# BRD171031.net
KiCad netlist of a schematic drawn in EAGLE
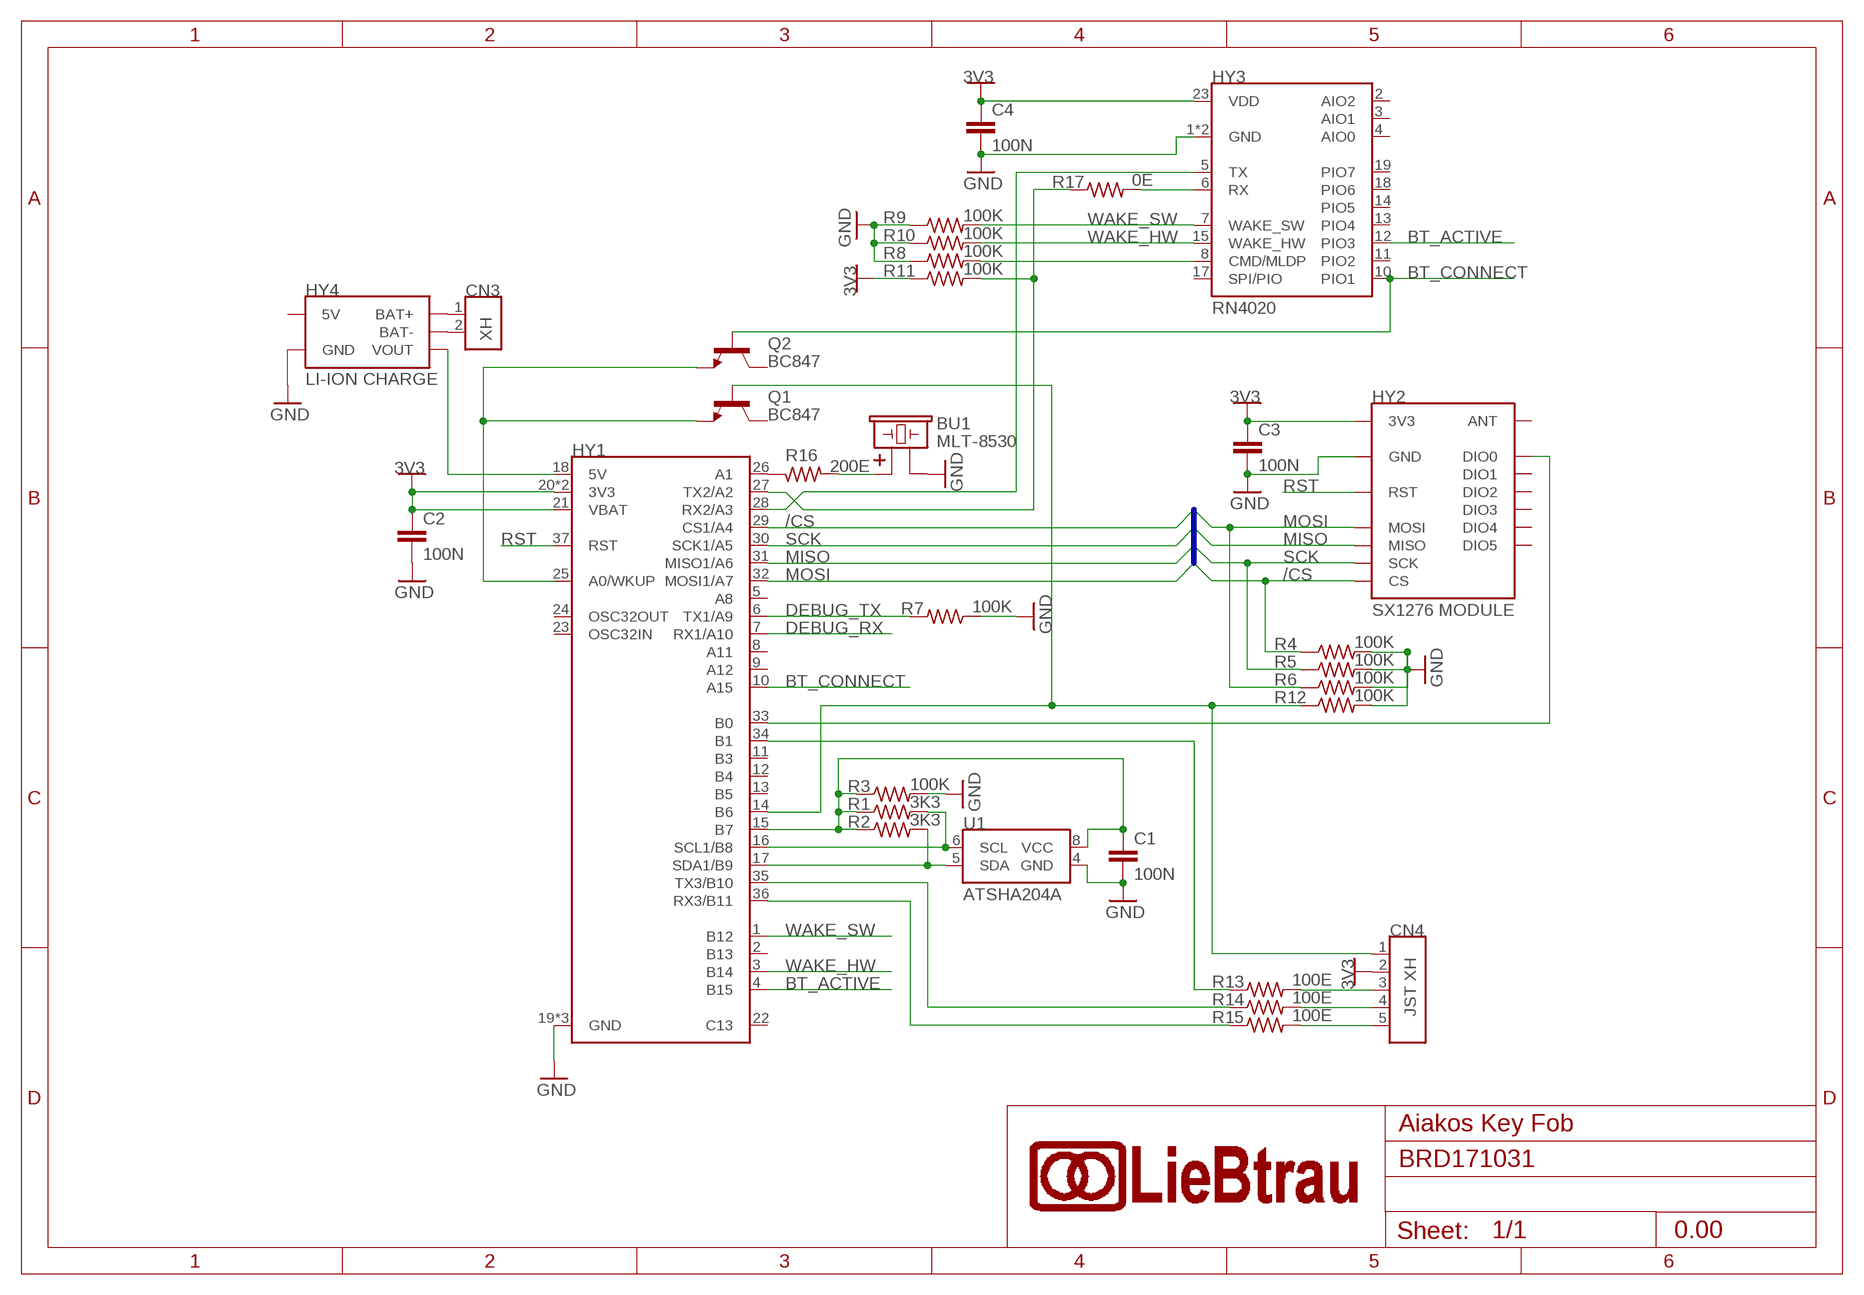
[diagram p0: schematic, sheet 1]

(export (version "E")
  (design (tool "Eeschema 10.0.6"))
  (components
    (comp (ref "BU1")
      (value "MLT-8530")
      (footprint "eagle-import:BU_8530")
      (libsource (lib "eagle-import") (part "BU_B2P8530_8530_"))
    )
    (comp (ref "C1")
      (value "100N")
      (footprint "eagle-import:CA_1206")
      (libsource (lib "eagle-import") (part "CA1206_100N_"))
    )
    (comp (ref "C2")
      (value "100N")
      (footprint "eagle-import:CA_1206")
      (libsource (lib "eagle-import") (part "CA1206_100N_"))
    )
    (comp (ref "C3")
      (value "100N")
      (footprint "eagle-import:CA_1206")
      (libsource (lib "eagle-import") (part "CA1206_100N_"))
    )
    (comp (ref "C4")
      (value "100N")
      (footprint "eagle-import:CA_1206")
      (libsource (lib "eagle-import") (part "CA1206_100N_"))
    )
    (comp (ref "CN3")
      (value "XH")
      (footprint "eagle-import:CN_HDR_1X2_180D_P25_JST_B2B-XH")
      (libsource (lib "eagle-import") (part "CN_2PJST_B2B-XH_JST_B2B-XH_"))
    )
    (comp (ref "CN4")
      (value "JST XH")
      (footprint "eagle-import:CN_HDR_1X5_180D_P25_JST_B5B-XH")
      (libsource (lib "eagle-import") (part "CN_5PJST_B5B-XH_JST_B5B-XH_"))
    )
    (comp (ref "HY1")
      (value "HY_DEVBRD_BLUEPILL")
      (footprint "eagle-import:HY_DEVBRD_BLUEPILL_SMD")
      (libsource (lib "eagle-import") (part "HY_DEVBRD_BLUEPILL"))
    )
    (comp (ref "HY2")
      (value "SX1276 MODULE")
      (footprint "eagle-import:HY_SX1276")
      (libsource (lib "eagle-import") (part "HY_SX1276"))
    )
    (comp (ref "HY3")
      (value "RN4020")
      (footprint "eagle-import:HY_BLE_RN4020")
      (libsource (lib "eagle-import") (part "HY_RF_BLE_RN4020"))
    )
    (comp (ref "HY4")
      (value "LI-ION CHARGE")
      (footprint "eagle-import:HY_PMMOD_LIION")
      (libsource (lib "eagle-import") (part "HY_PMMOD_LIION_TP4056__TP4056_"))
    )
    (comp (ref "Q1")
      (value "BC847")
      (footprint "eagle-import:SC_SOT23")
      (libsource (lib "eagle-import") (part "TR_NPNSOT23_BC847_"))
    )
    (comp (ref "Q2")
      (value "BC847")
      (footprint "eagle-import:SC_SOT23")
      (libsource (lib "eagle-import") (part "TR_NPNSOT23_BC847_"))
    )
    (comp (ref "R1")
      (value "3K3")
      (footprint "eagle-import:RE_1206")
      (libsource (lib "eagle-import") (part "RE1206_3K3_"))
    )
    (comp (ref "R2")
      (value "3K3")
      (footprint "eagle-import:RE_1206")
      (libsource (lib "eagle-import") (part "RE1206_3K3_"))
    )
    (comp (ref "R3")
      (value "100K")
      (footprint "eagle-import:RE_1206")
      (libsource (lib "eagle-import") (part "RE1206_100K_"))
    )
    (comp (ref "R4")
      (value "100K")
      (footprint "eagle-import:RE_1206")
      (libsource (lib "eagle-import") (part "RE1206_100K_"))
    )
    (comp (ref "R5")
      (value "100K")
      (footprint "eagle-import:RE_1206")
      (libsource (lib "eagle-import") (part "RE1206_100K_"))
    )
    (comp (ref "R6")
      (value "100K")
      (footprint "eagle-import:RE_1206")
      (libsource (lib "eagle-import") (part "RE1206_100K_"))
    )
    (comp (ref "R7")
      (value "100K")
      (footprint "eagle-import:RE_1206")
      (libsource (lib "eagle-import") (part "RE1206_100K_"))
    )
    (comp (ref "R8")
      (value "100K")
      (footprint "eagle-import:RE_1206")
      (libsource (lib "eagle-import") (part "RE1206_100K_"))
    )
    (comp (ref "R9")
      (value "100K")
      (footprint "eagle-import:RE_1206")
      (libsource (lib "eagle-import") (part "RE1206_100K_"))
    )
    (comp (ref "R10")
      (value "100K")
      (footprint "eagle-import:RE_1206")
      (libsource (lib "eagle-import") (part "RE1206_100K_"))
    )
    (comp (ref "R11")
      (value "100K")
      (footprint "eagle-import:RE_1206")
      (libsource (lib "eagle-import") (part "RE1206_100K_"))
    )
    (comp (ref "R12")
      (value "100K")
      (footprint "eagle-import:RE_1206")
      (libsource (lib "eagle-import") (part "RE1206_100K_"))
    )
    (comp (ref "R13")
      (value "100E")
      (footprint "eagle-import:RE_1206")
      (libsource (lib "eagle-import") (part "RE1206_100E_"))
    )
    (comp (ref "R14")
      (value "100E")
      (footprint "eagle-import:RE_1206")
      (libsource (lib "eagle-import") (part "RE1206_100E_"))
    )
    (comp (ref "R15")
      (value "100E")
      (footprint "eagle-import:RE_1206")
      (libsource (lib "eagle-import") (part "RE1206_100E_"))
    )
    (comp (ref "R16")
      (value "200E")
      (footprint "eagle-import:RE_1206")
      (libsource (lib "eagle-import") (part "RE1206_200E_"))
    )
    (comp (ref "R17")
      (value "0E")
      (footprint "eagle-import:RE_1206")
      (libsource (lib "eagle-import") (part "RE1206_0E_"))
    )
    (comp (ref "U1")
      (value "ATSHA204A")
      (footprint "eagle-import:SC_SO08")
      (libsource (lib "eagle-import") (part "IC_SPEC_ATSHA204A_SO8_ATSHA204A_"))
    )
  )
  (nets
    (net (code "1") (name "/BT_ACTIVE") (class "Default")
      (node (ref "HY1") (pin "4") (pinfunction "B15_4") (pintype "bidirectional"))
      (node (ref "HY3") (pin "12") (pinfunction "PIO3_12") (pintype "bidirectional"))
    )
    (net (code "2") (name "/BT_CONNECT") (class "Default")
      (node (ref "HY1") (pin "10") (pinfunction "A15_10") (pintype "bidirectional"))
      (node (ref "HY3") (pin "10") (pinfunction "PIO1_10") (pintype "bidirectional"))
      (node (ref "Q2") (pin "1") (pinfunction "B_1") (pintype "passive"))
    )
    (net (code "3") (name "/DEBUG_RX") (class "Default")
      (node (ref "HY1") (pin "7") (pinfunction "RX1/A10_7") (pintype "bidirectional"))
    )
    (net (code "4") (name "/DEBUG_TX") (class "Default")
      (node (ref "HY1") (pin "6") (pinfunction "TX1/A9_6") (pintype "bidirectional"))
      (node (ref "R7") (pin "2") (pinfunction "2_2") (pintype "passive"))
    )
    (net (code "5") (name "/MISO") (class "Default")
      (node (ref "HY1") (pin "31") (pinfunction "MISO1/A6_31") (pintype "bidirectional"))
      (node (ref "HY2") (pin "MISO") (pinfunction "MISO_MISO") (pintype "bidirectional"))
    )
    (net (code "6") (name "/MOSI") (class "Default")
      (node (ref "HY1") (pin "32") (pinfunction "MOSI1/A7_32") (pintype "bidirectional"))
      (node (ref "HY2") (pin "MOSI") (pinfunction "MOSI_MOSI") (pintype "bidirectional"))
      (node (ref "R6") (pin "1") (pinfunction "1_1") (pintype "passive"))
    )
    (net (code "7") (name "/RST") (class "Default")
      (node (ref "HY1") (pin "37") (pinfunction "RST_37") (pintype "bidirectional"))
      (node (ref "HY2") (pin "REST") (pinfunction "RST_REST") (pintype "bidirectional"))
    )
    (net (code "8") (name "/SCK") (class "Default")
      (node (ref "HY1") (pin "30") (pinfunction "SCK1/A5_30") (pintype "bidirectional"))
      (node (ref "HY2") (pin "SCK") (pinfunction "SCK_SCK") (pintype "bidirectional"))
      (node (ref "R5") (pin "1") (pinfunction "1_1") (pintype "passive"))
    )
    (net (code "9") (name "/WAKE_HW") (class "Default")
      (node (ref "HY1") (pin "3") (pinfunction "B14_3") (pintype "bidirectional"))
      (node (ref "HY3") (pin "15") (pinfunction "WAKE_HW_15") (pintype "bidirectional"))
      (node (ref "R10") (pin "2") (pinfunction "2_2") (pintype "passive"))
    )
    (net (code "10") (name "/WAKE_SW") (class "Default")
      (node (ref "HY1") (pin "1") (pinfunction "B12_1") (pintype "bidirectional"))
      (node (ref "HY3") (pin "7") (pinfunction "WAKE_SW_7") (pintype "bidirectional"))
      (node (ref "R9") (pin "2") (pinfunction "2_2") (pintype "passive"))
    )
    (net (code "11") (name "/{slash}CS") (class "Default")
      (node (ref "HY1") (pin "29") (pinfunction "CS1/A4_29") (pintype "bidirectional"))
      (node (ref "HY2") (pin "NSS") (pinfunction "CS_NSS") (pintype "bidirectional"))
      (node (ref "R4") (pin "1") (pinfunction "1_1") (pintype "passive"))
    )
    (net (code "12") (name "3V3") (class "Default")
      (node (ref "C2") (pin "1") (pinfunction "1_1") (pintype "passive"))
      (node (ref "C3") (pin "1") (pinfunction "1_1") (pintype "passive"))
      (node (ref "C4") (pin "1") (pinfunction "1_1") (pintype "passive"))
      (node (ref "CN4") (pin "2") (pinfunction "2_2") (pintype "bidirectional"))
      (node (ref "HY1") (pin "20") (pinfunction "3V3_20") (pintype "bidirectional"))
      (node (ref "HY1") (pin "21") (pinfunction "VBAT_21") (pintype "bidirectional"))
      (node (ref "HY1") (pin "38") (pinfunction "3V3_38") (pintype "bidirectional"))
      (node (ref "HY2") (pin "VCC") (pinfunction "3V3_VCC") (pintype "bidirectional"))
      (node (ref "HY3") (pin "23") (pinfunction "VDD_23") (pintype "bidirectional"))
      (node (ref "R11") (pin "1") (pinfunction "1_1") (pintype "passive"))
    )
    (net (code "13") (name "GND") (class "Default")
      (node (ref "BU1") (pin "2") (pinfunction "2_2") (pintype "passive"))
      (node (ref "C1") (pin "2") (pinfunction "2_2") (pintype "passive"))
      (node (ref "C2") (pin "2") (pinfunction "2_2") (pintype "passive"))
      (node (ref "C3") (pin "2") (pinfunction "2_2") (pintype "passive"))
      (node (ref "C4") (pin "2") (pinfunction "2_2") (pintype "passive"))
      (node (ref "HY1") (pin "19") (pinfunction "GND_19") (pintype "bidirectional"))
      (node (ref "HY1") (pin "39") (pinfunction "GND_39") (pintype "bidirectional"))
      (node (ref "HY1") (pin "40") (pinfunction "GND_40") (pintype "bidirectional"))
      (node (ref "HY2") (pin "GND") (pinfunction "GND_GND") (pintype "bidirectional"))
      (node (ref "HY2") (pin "GND@1") (pinfunction "GND_GND@1") (pintype "bidirectional"))
      (node (ref "HY2") (pin "GND@2") (pinfunction "GND_GND@2") (pintype "bidirectional"))
      (node (ref "HY3") (pin "1") (pinfunction "GND_1") (pintype "bidirectional"))
      (node (ref "HY3") (pin "24") (pinfunction "GND_24") (pintype "bidirectional"))
      (node (ref "HY4") (pin "GND1") (pinfunction "GND_GND1") (pintype "bidirectional"))
      (node (ref "HY4") (pin "GND2") (pinfunction "GND_GND2") (pintype "bidirectional"))
      (node (ref "R10") (pin "1") (pinfunction "1_1") (pintype "passive"))
      (node (ref "R12") (pin "2") (pinfunction "2_2") (pintype "passive"))
      (node (ref "R3") (pin "2") (pinfunction "2_2") (pintype "passive"))
      (node (ref "R4") (pin "2") (pinfunction "2_2") (pintype "passive"))
      (node (ref "R5") (pin "2") (pinfunction "2_2") (pintype "passive"))
      (node (ref "R6") (pin "2") (pinfunction "2_2") (pintype "passive"))
      (node (ref "R7") (pin "1") (pinfunction "1_1") (pintype "passive"))
      (node (ref "R8") (pin "1") (pinfunction "1_1") (pintype "passive"))
      (node (ref "R9") (pin "1") (pinfunction "1_1") (pintype "passive"))
      (node (ref "U1") (pin "4") (pinfunction "GND_4") (pintype "bidirectional"))
    )
    (net (code "14") (name "Net-(BU1-Pad1)") (class "Default")
      (node (ref "BU1") (pin "1") (pinfunction "1_1") (pintype "passive"))
      (node (ref "R16") (pin "2") (pinfunction "2_2") (pintype "passive"))
    )
    (net (code "15") (name "Net-(CN4-Pad3)") (class "Default")
      (node (ref "CN4") (pin "3") (pinfunction "3_3") (pintype "bidirectional"))
      (node (ref "R13") (pin "2") (pinfunction "2_2") (pintype "passive"))
    )
    (net (code "16") (name "Net-(CN4-Pad4)") (class "Default")
      (node (ref "CN4") (pin "4") (pinfunction "4_4") (pintype "bidirectional"))
      (node (ref "R14") (pin "2") (pinfunction "2_2") (pintype "passive"))
    )
    (net (code "17") (name "Net-(CN4-Pad5)") (class "Default")
      (node (ref "CN4") (pin "5") (pinfunction "5_5") (pintype "bidirectional"))
      (node (ref "R15") (pin "2") (pinfunction "2_2") (pintype "passive"))
    )
    (net (code "18") (name "Net-(HY1-5V)") (class "Default")
      (node (ref "HY1") (pin "18") (pinfunction "5V_18") (pintype "bidirectional"))
      (node (ref "HY4") (pin "OUT+") (pinfunction "VOUT_OUT+") (pintype "bidirectional"))
    )
    (net (code "19") (name "Net-(HY1-A0{slash}WKUP)") (class "Default")
      (node (ref "HY1") (pin "25") (pinfunction "A0/WKUP_25") (pintype "bidirectional"))
      (node (ref "Q1") (pin "2") (pinfunction "E_2") (pintype "passive"))
      (node (ref "Q2") (pin "2") (pinfunction "E_2") (pintype "passive"))
    )
    (net (code "20") (name "Net-(HY1-A1)") (class "Default")
      (node (ref "HY1") (pin "26") (pinfunction "A1_26") (pintype "bidirectional"))
      (node (ref "R16") (pin "1") (pinfunction "1_1") (pintype "passive"))
    )
    (net (code "21") (name "Net-(HY1-B0)") (class "Default")
      (node (ref "HY1") (pin "33") (pinfunction "B0_33") (pintype "bidirectional"))
      (node (ref "HY2") (pin "DIO0") (pinfunction "DIO0_DIO0") (pintype "bidirectional"))
    )
    (net (code "22") (name "Net-(HY1-B1)") (class "Default")
      (node (ref "HY1") (pin "34") (pinfunction "B1_34") (pintype "bidirectional"))
      (node (ref "R13") (pin "1") (pinfunction "1_1") (pintype "passive"))
    )
    (net (code "23") (name "Net-(HY1-B6)") (class "Default")
      (node (ref "CN4") (pin "1") (pinfunction "1_1") (pintype "bidirectional"))
      (node (ref "HY1") (pin "14") (pinfunction "B6_14") (pintype "bidirectional"))
      (node (ref "Q1") (pin "1") (pinfunction "B_1") (pintype "passive"))
      (node (ref "R12") (pin "1") (pinfunction "1_1") (pintype "passive"))
    )
    (net (code "24") (name "Net-(HY1-B7)") (class "Default")
      (node (ref "C1") (pin "1") (pinfunction "1_1") (pintype "passive"))
      (node (ref "HY1") (pin "15") (pinfunction "B7_15") (pintype "bidirectional"))
      (node (ref "R1") (pin "1") (pinfunction "1_1") (pintype "passive"))
      (node (ref "R2") (pin "1") (pinfunction "1_1") (pintype "passive"))
      (node (ref "R3") (pin "1") (pinfunction "1_1") (pintype "passive"))
      (node (ref "U1") (pin "8") (pinfunction "VCC_8") (pintype "bidirectional"))
    )
    (net (code "25") (name "Net-(HY1-RX2{slash}A3)") (class "Default")
      (node (ref "HY1") (pin "28") (pinfunction "RX2/A3_28") (pintype "bidirectional"))
      (node (ref "HY3") (pin "5") (pinfunction "TX_5") (pintype "bidirectional"))
    )
    (net (code "26") (name "Net-(HY1-RX3{slash}B11)") (class "Default")
      (node (ref "HY1") (pin "36") (pinfunction "RX3/B11_36") (pintype "bidirectional"))
      (node (ref "R15") (pin "1") (pinfunction "1_1") (pintype "passive"))
    )
    (net (code "27") (name "Net-(HY1-SCL1{slash}B8)") (class "Default")
      (node (ref "HY1") (pin "16") (pinfunction "SCL1/B8_16") (pintype "bidirectional"))
      (node (ref "R1") (pin "2") (pinfunction "2_2") (pintype "passive"))
      (node (ref "U1") (pin "6") (pinfunction "SCL_6") (pintype "bidirectional"))
    )
    (net (code "28") (name "Net-(HY1-SDA1{slash}B9)") (class "Default")
      (node (ref "HY1") (pin "17") (pinfunction "SDA1/B9_17") (pintype "bidirectional"))
      (node (ref "R2") (pin "2") (pinfunction "2_2") (pintype "passive"))
      (node (ref "U1") (pin "5") (pinfunction "SDA_5") (pintype "bidirectional"))
    )
    (net (code "29") (name "Net-(HY1-TX2{slash}A2)") (class "Default")
      (node (ref "HY1") (pin "27") (pinfunction "TX2/A2_27") (pintype "bidirectional"))
      (node (ref "R11") (pin "2") (pinfunction "2_2") (pintype "passive"))
      (node (ref "R17") (pin "1") (pinfunction "1_1") (pintype "passive"))
    )
    (net (code "30") (name "Net-(HY1-TX3{slash}B10)") (class "Default")
      (node (ref "HY1") (pin "35") (pinfunction "TX3/B10_35") (pintype "bidirectional"))
      (node (ref "R14") (pin "1") (pinfunction "1_1") (pintype "passive"))
    )
    (net (code "31") (name "Net-(HY3-CMD{slash}MLDP)") (class "Default")
      (node (ref "HY3") (pin "8") (pinfunction "CMD/MLDP_8") (pintype "bidirectional"))
      (node (ref "R8") (pin "2") (pinfunction "2_2") (pintype "passive"))
    )
    (net (code "32") (name "Net-(HY3-RX)") (class "Default")
      (node (ref "HY3") (pin "6") (pinfunction "RX_6") (pintype "bidirectional"))
      (node (ref "R17") (pin "2") (pinfunction "2_2") (pintype "passive"))
    )
    (net (code "33") (name "Net-(HY4-BAT+)") (class "Default")
      (node (ref "CN3") (pin "1") (pinfunction "1_1") (pintype "bidirectional"))
      (node (ref "HY4") (pin "B+") (pinfunction "BAT+_B+") (pintype "bidirectional"))
    )
    (net (code "34") (name "Net-(HY4-BAT-)") (class "Default")
      (node (ref "CN3") (pin "2") (pinfunction "2_2") (pintype "bidirectional"))
      (node (ref "HY4") (pin "B-") (pinfunction "BAT-_B-") (pintype "bidirectional"))
    )
    (net (code "35") (name "unconnected-(HY1-A8-Pad5)") (class "Default")
      (node (ref "HY1") (pin "5") (pinfunction "A8_5") (pintype "bidirectional"))
    )
    (net (code "36") (name "unconnected-(HY1-A11-Pad8)") (class "Default")
      (node (ref "HY1") (pin "8") (pinfunction "A11_8") (pintype "bidirectional"))
    )
    (net (code "37") (name "unconnected-(HY1-A12-Pad9)") (class "Default")
      (node (ref "HY1") (pin "9") (pinfunction "A12_9") (pintype "bidirectional"))
    )
    (net (code "38") (name "unconnected-(HY1-B3-Pad11)") (class "Default")
      (node (ref "HY1") (pin "11") (pinfunction "B3_11") (pintype "bidirectional"))
    )
    (net (code "39") (name "unconnected-(HY1-B4-Pad12)") (class "Default")
      (node (ref "HY1") (pin "12") (pinfunction "B4_12") (pintype "bidirectional"))
    )
    (net (code "40") (name "unconnected-(HY1-B5-Pad13)") (class "Default")
      (node (ref "HY1") (pin "13") (pinfunction "B5_13") (pintype "bidirectional"))
    )
    (net (code "41") (name "unconnected-(HY1-B13-Pad2)") (class "Default")
      (node (ref "HY1") (pin "2") (pinfunction "B13_2") (pintype "bidirectional"))
    )
    (net (code "42") (name "unconnected-(HY1-C13-Pad22)") (class "Default")
      (node (ref "HY1") (pin "22") (pinfunction "C13_22") (pintype "bidirectional"))
    )
    (net (code "43") (name "unconnected-(HY1-OSC32IN-Pad23)") (class "Default")
      (node (ref "HY1") (pin "23") (pinfunction "OSC32IN_23") (pintype "bidirectional"))
    )
    (net (code "44") (name "unconnected-(HY1-OSC32OUT-Pad24)") (class "Default")
      (node (ref "HY1") (pin "24") (pinfunction "OSC32OUT_24") (pintype "bidirectional"))
    )
    (net (code "45") (name "unconnected-(HY2-PadANT)") (class "Default")
      (node (ref "HY2") (pin "ANT") (pinfunction "ANT_ANT") (pintype "bidirectional"))
    )
    (net (code "46") (name "unconnected-(HY2-PadDIO1)") (class "Default")
      (node (ref "HY2") (pin "DIO1") (pinfunction "DIO1_DIO1") (pintype "bidirectional"))
    )
    (net (code "47") (name "unconnected-(HY2-PadDIO2)") (class "Default")
      (node (ref "HY2") (pin "DIO2") (pinfunction "DIO2_DIO2") (pintype "bidirectional"))
    )
    (net (code "48") (name "unconnected-(HY2-PadDIO3)") (class "Default")
      (node (ref "HY2") (pin "DIO3") (pinfunction "DIO3_DIO3") (pintype "bidirectional"))
    )
    (net (code "49") (name "unconnected-(HY2-PadDIO4)") (class "Default")
      (node (ref "HY2") (pin "DIO4") (pinfunction "DIO4_DIO4") (pintype "bidirectional"))
    )
    (net (code "50") (name "unconnected-(HY2-PadDIO5)") (class "Default")
      (node (ref "HY2") (pin "DIO5") (pinfunction "DIO5_DIO5") (pintype "bidirectional"))
    )
    (net (code "51") (name "unconnected-(HY3-AIO0-Pad4)") (class "Default")
      (node (ref "HY3") (pin "4") (pinfunction "AIO0_4") (pintype "bidirectional"))
    )
    (net (code "52") (name "unconnected-(HY3-AIO1-Pad3)") (class "Default")
      (node (ref "HY3") (pin "3") (pinfunction "AIO1_3") (pintype "bidirectional"))
    )
    (net (code "53") (name "unconnected-(HY3-AIO2-Pad2)") (class "Default")
      (node (ref "HY3") (pin "2") (pinfunction "AIO2_2") (pintype "bidirectional"))
    )
    (net (code "54") (name "unconnected-(HY3-PIO2-Pad11)") (class "Default")
      (node (ref "HY3") (pin "11") (pinfunction "PIO2_11") (pintype "bidirectional"))
    )
    (net (code "55") (name "unconnected-(HY3-PIO4-Pad13)") (class "Default")
      (node (ref "HY3") (pin "13") (pinfunction "PIO4_13") (pintype "bidirectional"))
    )
    (net (code "56") (name "unconnected-(HY3-PIO5-Pad14)") (class "Default")
      (node (ref "HY3") (pin "14") (pinfunction "PIO5_14") (pintype "bidirectional"))
    )
    (net (code "57") (name "unconnected-(HY3-PIO6-Pad18)") (class "Default")
      (node (ref "HY3") (pin "18") (pinfunction "PIO6_18") (pintype "bidirectional"))
    )
    (net (code "58") (name "unconnected-(HY3-PIO7-Pad19)") (class "Default")
      (node (ref "HY3") (pin "19") (pinfunction "PIO7_19") (pintype "bidirectional"))
    )
    (net (code "59") (name "unconnected-(HY3-SPI{slash}PIO-Pad17)") (class "Default")
      (node (ref "HY3") (pin "17") (pinfunction "SPI/PIO_17") (pintype "bidirectional"))
    )
    (net (code "60") (name "unconnected-(HY4-Pad5V)") (class "Default")
      (node (ref "HY4") (pin "5V") (pinfunction "5V_5V") (pintype "bidirectional"))
    )
    (net (code "61") (name "unconnected-(Q1-C-Pad3)") (class "Default")
      (node (ref "Q1") (pin "3") (pinfunction "C_3") (pintype "passive"))
    )
    (net (code "62") (name "unconnected-(Q2-C-Pad3)") (class "Default")
      (node (ref "Q2") (pin "3") (pinfunction "C_3") (pintype "passive"))
    )
  )
)
